# node.net
KiCad netlist of a schematic drawn in EAGLE
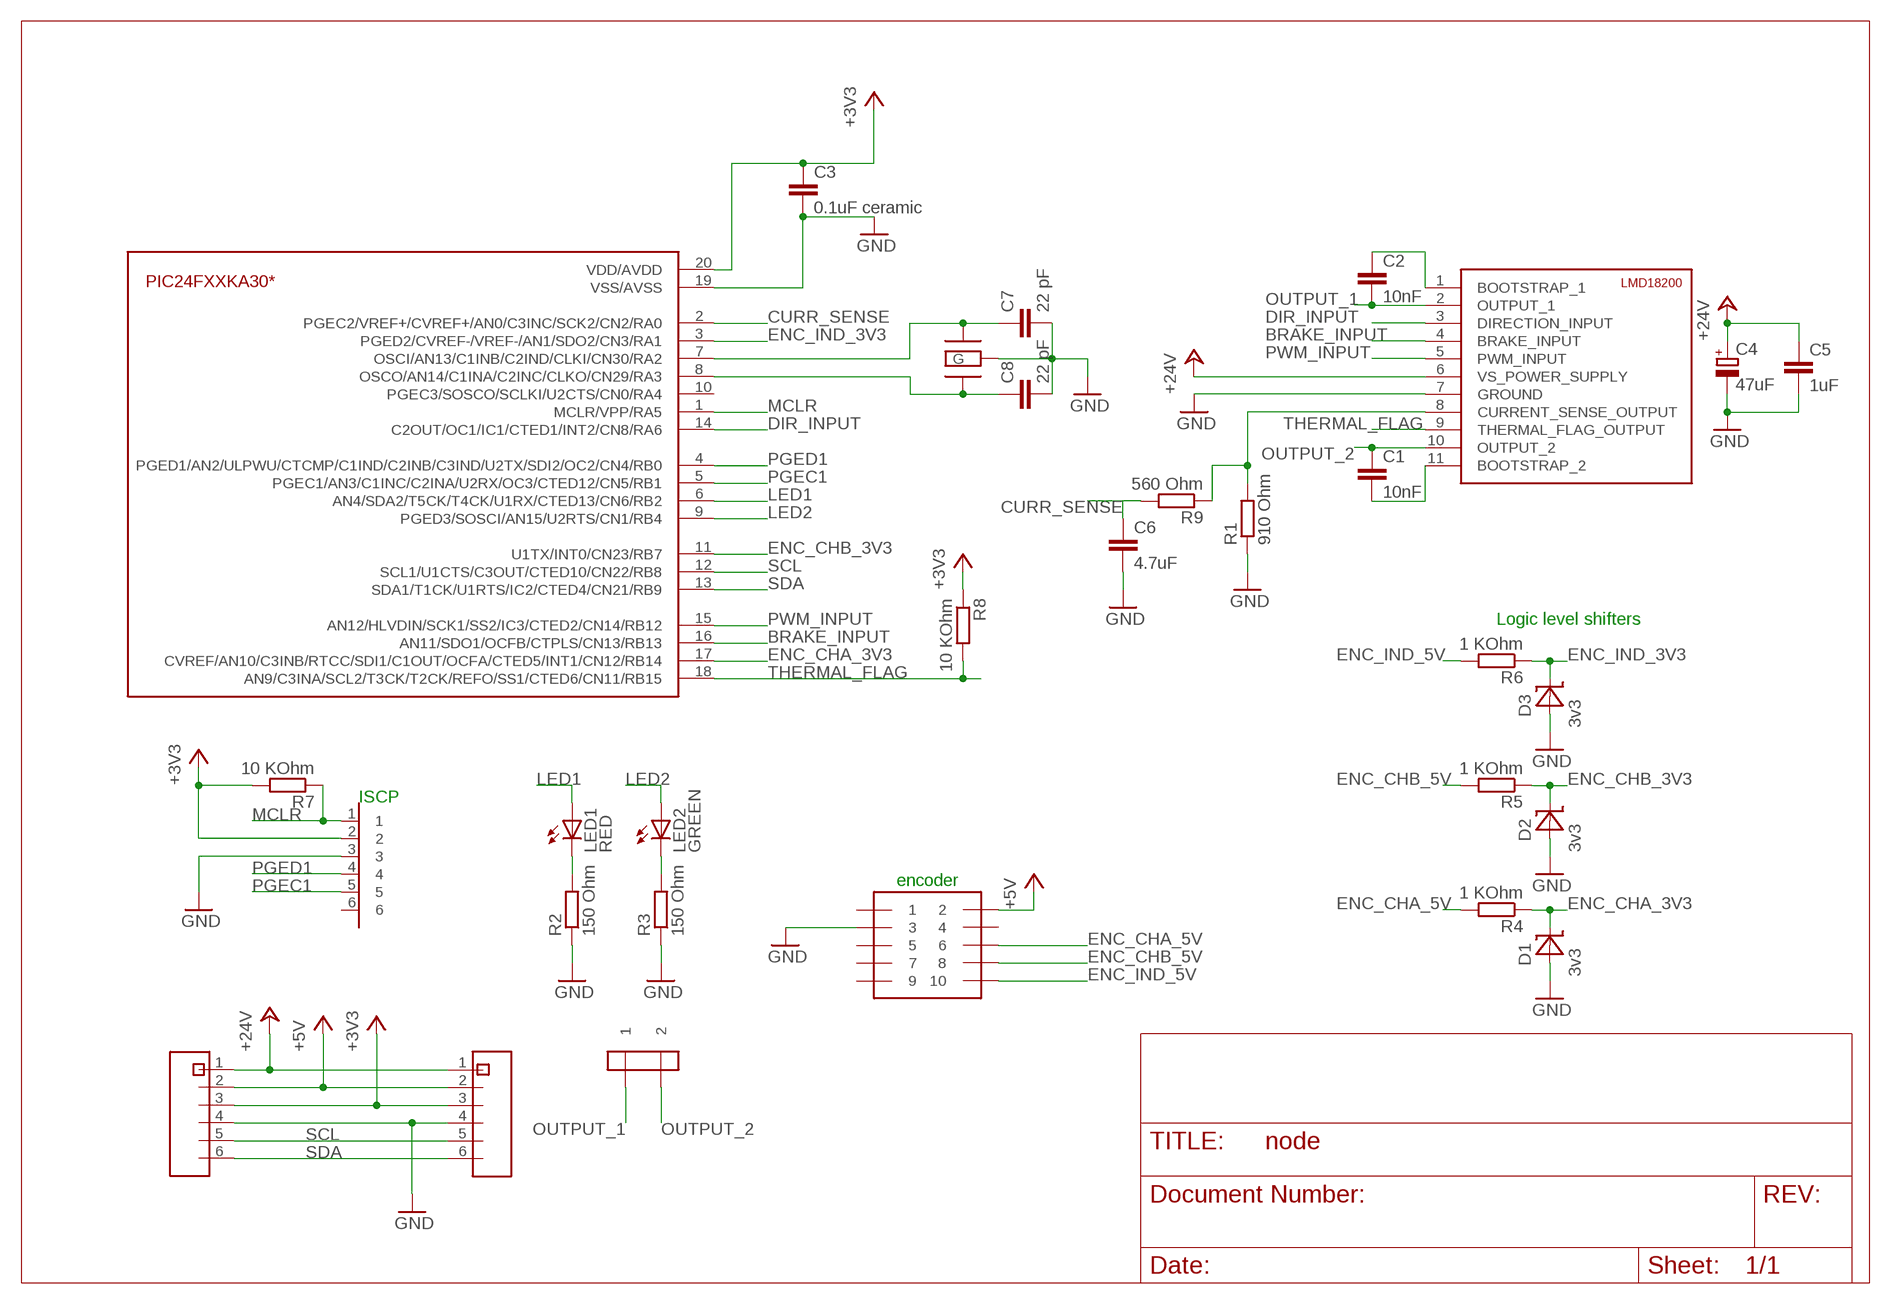
[diagram p0: schematic, sheet 1]

(export (version "E")
  (design (tool "Eeschema 10.0.6"))
  (components
    (comp (ref "C1")
      (value "10nF")
      (footprint "eagle-import:C0603")
      (libsource (lib "eagle-import") (part "resistor_C-EUC0603"))
    )
    (comp (ref "C2")
      (value "10nF")
      (footprint "eagle-import:C0603")
      (libsource (lib "eagle-import") (part "resistor_C-EUC0603"))
    )
    (comp (ref "C3")
      (value "0.1uF ceramic")
      (footprint "eagle-import:C0805K")
      (libsource (lib "eagle-import") (part "resistor_C-EUC0805K"))
    )
    (comp (ref "C4")
      (value "47uF")
      (footprint "eagle-import:E5-10,5")
      (libsource (lib "eagle-import") (part "CPOL-EUE5-10.5"))
    )
    (comp (ref "C5")
      (value "1uF")
      (footprint "eagle-import:C050-025X075")
      (libsource (lib "eagle-import") (part "C-EU050-025X075"))
    )
    (comp (ref "C6")
      (value "4.7uF")
      (footprint "eagle-import:C0805K")
      (libsource (lib "eagle-import") (part "resistor_C-EUC0805K"))
    )
    (comp (ref "C7")
      (value "22 pF")
      (footprint "eagle-import:C0603")
      (libsource (lib "eagle-import") (part "C-EUC0603"))
    )
    (comp (ref "C8")
      (value "22 pF")
      (footprint "eagle-import:C0603")
      (libsource (lib "eagle-import") (part "C-EUC0603"))
    )
    (comp (ref "D1")
      (value "3v3")
      (footprint "eagle-import:SOD-323")
      (libsource (lib "eagle-import") (part "ZENER_SOD323"))
    )
    (comp (ref "D2")
      (value "3v3")
      (footprint "eagle-import:SOD-323")
      (libsource (lib "eagle-import") (part "ZENER_SOD323"))
    )
    (comp (ref "D3")
      (value "3v3")
      (footprint "eagle-import:SOD-323")
      (libsource (lib "eagle-import") (part "ZENER_SOD323"))
    )
    (comp (ref "LED1")
      (value "RED")
      (footprint "eagle-import:CHIPLED_1206")
      (libsource (lib "eagle-import") (part "LEDCHIPLED_1206"))
    )
    (comp (ref "LED2")
      (value "GREEN")
      (footprint "eagle-import:CHIPLED_1206")
      (libsource (lib "eagle-import") (part "LEDCHIPLED_1206"))
    )
    (comp (ref "R1")
      (value "910 Ohm")
      (footprint "eagle-import:R0603")
      (libsource (lib "eagle-import") (part "R-EU_R0603"))
    )
    (comp (ref "R2")
      (value "150 Ohm")
      (footprint "eagle-import:R0603")
      (libsource (lib "eagle-import") (part "R-EU_R0603"))
    )
    (comp (ref "R3")
      (value "150 Ohm")
      (footprint "eagle-import:R0603")
      (libsource (lib "eagle-import") (part "R-EU_R0603"))
    )
    (comp (ref "R4")
      (value "1 KOhm")
      (footprint "eagle-import:R0603")
      (libsource (lib "eagle-import") (part "R-EU_R0603"))
    )
    (comp (ref "R5")
      (value "1 KOhm")
      (footprint "eagle-import:R0603")
      (libsource (lib "eagle-import") (part "R-EU_R0603"))
    )
    (comp (ref "R6")
      (value "1 KOhm")
      (footprint "eagle-import:R0603")
      (libsource (lib "eagle-import") (part "R-EU_R0603"))
    )
    (comp (ref "R7")
      (value "10 KOhm")
      (footprint "eagle-import:R0603")
      (libsource (lib "eagle-import") (part "R-EU_R0603"))
    )
    (comp (ref "R8")
      (value "10 KOhm")
      (footprint "eagle-import:R0603")
      (libsource (lib "eagle-import") (part "R-EU_R0603"))
    )
    (comp (ref "R9")
      (value "560 Ohm")
      (footprint "eagle-import:R0603")
      (libsource (lib "eagle-import") (part "R-EU_R0603"))
    )
    (comp (ref "U$1")
      (value "PIC24F32KA301")
      (footprint "eagle-import:SSOP-20")
      (libsource (lib "eagle-import") (part "PIC24F32KA301"))
    )
    (comp (ref "U$2")
      (value "LMD18200")
      (footprint "eagle-import:TO-220-11")
      (libsource (lib "eagle-import") (part "LMD18200"))
    )
    (comp (ref "U$3")
      (value "MOLEX_3.96MM_6P")
      (footprint "eagle-import:MOLEX_3.96MM_6P")
      (libsource (lib "eagle-import") (part "MOLEX_3.96MM_6P"))
    )
    (comp (ref "U$4")
      (value "MOLEX_3.96MM_6P")
      (footprint "eagle-import:MOLEX_3.96MM_6P")
      (libsource (lib "eagle-import") (part "MOLEX_3.96MM_6P"))
    )
    (comp (ref "U$5")
      (value "DIN41651_10P")
      (footprint "eagle-import:DIN41651_10P")
      (libsource (lib "eagle-import") (part "DIN41651_10P"))
    )
    (comp (ref "U$6")
      (value "STIFTLIST_6X1P")
      (footprint "eagle-import:STIFTLIST_6X1P")
      (libsource (lib "eagle-import") (part "STIFTLIST_6X1P"))
    )
    (comp (ref "U$7")
      (value "CRYSTAL_ELFA")
      (footprint "eagle-import:CRYSTAL_SMD")
      (libsource (lib "eagle-import") (part "CRYSTAL_ELFA"))
    )
    (comp (ref "U$8")
      (value "PCB_SKRUVPLINT_2P")
      (footprint "eagle-import:PCB_SKRUVPLINT_2P")
      (libsource (lib "eagle-import") (part "PCB_SKRUVPLINT_2P"))
    )
  )
  (nets
    (net (code "1") (name "+3V3") (class "Default")
      (node (ref "C3") (pin "1") (pinfunction "1_1") (pintype "passive"))
      (node (ref "R7") (pin "2") (pinfunction "2_2") (pintype "passive"))
      (node (ref "R8") (pin "1") (pinfunction "1_1") (pintype "passive"))
      (node (ref "U$1") (pin "20") (pinfunction "VDD/AVDD_20") (pintype "bidirectional"))
      (node (ref "U$3") (pin "3") (pinfunction "3_3") (pintype "bidirectional"))
      (node (ref "U$4") (pin "3") (pinfunction "3_3") (pintype "bidirectional"))
      (node (ref "U$6") (pin "2") (pinfunction "2_2") (pintype "bidirectional"))
    )
    (net (code "2") (name "+5V") (class "Default")
      (node (ref "U$3") (pin "2") (pinfunction "2_2") (pintype "bidirectional"))
      (node (ref "U$4") (pin "2") (pinfunction "2_2") (pintype "bidirectional"))
      (node (ref "U$5") (pin "2") (pinfunction "2_2") (pintype "bidirectional"))
    )
    (net (code "3") (name "+24V") (class "Default")
      (node (ref "C4") (pin "+") (pinfunction "+_+") (pintype "passive"))
      (node (ref "C5") (pin "1") (pinfunction "1_1") (pintype "passive"))
      (node (ref "U$2") (pin "6") (pinfunction "VS_POWER_SUPPLY_6") (pintype "bidirectional"))
      (node (ref "U$3") (pin "1") (pinfunction "1_1") (pintype "bidirectional"))
      (node (ref "U$4") (pin "1") (pinfunction "1_1") (pintype "bidirectional"))
    )
    (net (code "4") (name "/BRAKE_INPUT") (class "Default")
      (node (ref "U$1") (pin "16") (pinfunction "AN11/SDO1/OCFB/CTPLS/CN13/RB13_16") (pintype "bidirectional"))
      (node (ref "U$2") (pin "4") (pinfunction "BRAKE_INPUT_4") (pintype "bidirectional"))
    )
    (net (code "5") (name "/CURR_SENSE") (class "Default")
      (node (ref "C6") (pin "1") (pinfunction "1_1") (pintype "passive"))
      (node (ref "R9") (pin "2") (pinfunction "2_2") (pintype "passive"))
      (node (ref "U$1") (pin "2") (pinfunction "PGEC2/VREF+/CVREF+/AN0/C3INC/SCK2/CN2/RA0_2") (pintype "bidirectional"))
    )
    (net (code "6") (name "/DIR_INPUT") (class "Default")
      (node (ref "U$1") (pin "14") (pinfunction "C2OUT/OC1/IC1/CTED1/INT2/CN8/RA6_14") (pintype "bidirectional"))
      (node (ref "U$2") (pin "3") (pinfunction "DIRECTION_INPUT_3") (pintype "bidirectional"))
    )
    (net (code "7") (name "/ENC_CHA_3V3") (class "Default")
      (node (ref "D1") (pin "C") (pinfunction "C_C") (pintype "passive"))
      (node (ref "R4") (pin "1") (pinfunction "1_1") (pintype "passive"))
      (node (ref "U$1") (pin "17") (pinfunction "CVREF/AN10/C3INB/RTCC/SDI1/C1OUT/OCFA/CTED5/INT1/CN12/RB14_17") (pintype "bidirectional"))
    )
    (net (code "8") (name "/ENC_CHA_5V") (class "Default")
      (node (ref "R4") (pin "2") (pinfunction "2_2") (pintype "passive"))
      (node (ref "U$5") (pin "6") (pinfunction "6_6") (pintype "bidirectional"))
    )
    (net (code "9") (name "/ENC_CHB_3V3") (class "Default")
      (node (ref "D2") (pin "C") (pinfunction "C_C") (pintype "passive"))
      (node (ref "R5") (pin "1") (pinfunction "1_1") (pintype "passive"))
      (node (ref "U$1") (pin "11") (pinfunction "U1TX/INT0/CN23/RB7_11") (pintype "bidirectional"))
    )
    (net (code "10") (name "/ENC_CHB_5V") (class "Default")
      (node (ref "R5") (pin "2") (pinfunction "2_2") (pintype "passive"))
      (node (ref "U$5") (pin "8") (pinfunction "8_8") (pintype "bidirectional"))
    )
    (net (code "11") (name "/ENC_IND_3V3") (class "Default")
      (node (ref "D3") (pin "C") (pinfunction "C_C") (pintype "passive"))
      (node (ref "R6") (pin "1") (pinfunction "1_1") (pintype "passive"))
      (node (ref "U$1") (pin "3") (pinfunction "PGED2/CVREF-/VREF-/AN1/SDO2/CN3/RA1_3") (pintype "bidirectional"))
    )
    (net (code "12") (name "/ENC_IND_5V") (class "Default")
      (node (ref "R6") (pin "2") (pinfunction "2_2") (pintype "passive"))
      (node (ref "U$5") (pin "10") (pinfunction "10_10") (pintype "bidirectional"))
    )
    (net (code "13") (name "/LED1") (class "Default")
      (node (ref "LED1") (pin "A") (pinfunction "A_A") (pintype "passive"))
      (node (ref "U$1") (pin "6") (pinfunction "AN4/SDA2/T5CK/T4CK/U1RX/CTED13/CN6/RB2_6") (pintype "bidirectional"))
    )
    (net (code "14") (name "/LED2") (class "Default")
      (node (ref "LED2") (pin "A") (pinfunction "A_A") (pintype "passive"))
      (node (ref "U$1") (pin "9") (pinfunction "PGED3/SOSCI/AN15/U2RTS/CN1/RB4_9") (pintype "bidirectional"))
    )
    (net (code "15") (name "/MCLR") (class "Default")
      (node (ref "R7") (pin "1") (pinfunction "1_1") (pintype "passive"))
      (node (ref "U$1") (pin "1") (pinfunction "MCLR/VPP/RA5_1") (pintype "bidirectional"))
      (node (ref "U$6") (pin "1") (pinfunction "1_1") (pintype "bidirectional"))
    )
    (net (code "16") (name "/OUTPUT_1") (class "Default")
      (node (ref "C2") (pin "2") (pinfunction "2_2") (pintype "passive"))
      (node (ref "U$2") (pin "2") (pinfunction "OUTPUT_1_2") (pintype "bidirectional"))
      (node (ref "U$8") (pin "1") (pinfunction "1_1") (pintype "bidirectional"))
    )
    (net (code "17") (name "/OUTPUT_2") (class "Default")
      (node (ref "C1") (pin "1") (pinfunction "1_1") (pintype "passive"))
      (node (ref "U$2") (pin "10") (pinfunction "OUTPUT_2_10") (pintype "bidirectional"))
      (node (ref "U$8") (pin "2") (pinfunction "2_2") (pintype "bidirectional"))
    )
    (net (code "18") (name "/PGEC1") (class "Default")
      (node (ref "U$1") (pin "5") (pinfunction "PGEC1/AN3/C1INC/C2INA/U2RX/OC3/CTED12/CN5/RB1_5") (pintype "bidirectional"))
      (node (ref "U$6") (pin "5") (pinfunction "5_5") (pintype "bidirectional"))
    )
    (net (code "19") (name "/PGED1") (class "Default")
      (node (ref "U$1") (pin "4") (pinfunction "PGED1/AN2/ULPWU/CTCMP/C1IND/C2INB/C3IND/U2TX/SDI2/OC2/CN4/RB0_4") (pintype "bidirectional"))
      (node (ref "U$6") (pin "4") (pinfunction "4_4") (pintype "bidirectional"))
    )
    (net (code "20") (name "/PWM_INPUT") (class "Default")
      (node (ref "U$1") (pin "15") (pinfunction "AN12/HLVDIN/SCK1/SS2/IC3/CTED2/CN14/RB12_15") (pintype "bidirectional"))
      (node (ref "U$2") (pin "5") (pinfunction "PWM_INPUT_5") (pintype "bidirectional"))
    )
    (net (code "21") (name "/SCL") (class "Default")
      (node (ref "U$1") (pin "12") (pinfunction "SCL1/U1CTS/C3OUT/CTED10/CN22/RB8_12") (pintype "bidirectional"))
      (node (ref "U$3") (pin "5") (pinfunction "5_5") (pintype "bidirectional"))
      (node (ref "U$4") (pin "5") (pinfunction "5_5") (pintype "bidirectional"))
    )
    (net (code "22") (name "/SDA") (class "Default")
      (node (ref "U$1") (pin "13") (pinfunction "SDA1/T1CK/U1RTS/IC2/CTED4/CN21/RB9_13") (pintype "bidirectional"))
      (node (ref "U$3") (pin "6") (pinfunction "6_6") (pintype "bidirectional"))
      (node (ref "U$4") (pin "6") (pinfunction "6_6") (pintype "bidirectional"))
    )
    (net (code "23") (name "/THERMAL_FLAG") (class "Default")
      (node (ref "R8") (pin "2") (pinfunction "2_2") (pintype "passive"))
      (node (ref "U$1") (pin "18") (pinfunction "AN9/C3INA/SCL2/T3CK/T2CK/REFO/SS1/CTED6/CN11/RB15_18") (pintype "bidirectional"))
      (node (ref "U$2") (pin "9") (pinfunction "THERMAL_FLAG_OUTPUT_9") (pintype "bidirectional"))
    )
    (net (code "24") (name "GND") (class "Default")
      (node (ref "C3") (pin "2") (pinfunction "2_2") (pintype "passive"))
      (node (ref "C4") (pin "-") (pinfunction "-_-") (pintype "passive"))
      (node (ref "C5") (pin "2") (pinfunction "2_2") (pintype "passive"))
      (node (ref "C6") (pin "2") (pinfunction "2_2") (pintype "passive"))
      (node (ref "C7") (pin "2") (pinfunction "2_2") (pintype "passive"))
      (node (ref "C8") (pin "2") (pinfunction "2_2") (pintype "passive"))
      (node (ref "D1") (pin "A") (pinfunction "A_A") (pintype "passive"))
      (node (ref "D2") (pin "A") (pinfunction "A_A") (pintype "passive"))
      (node (ref "D3") (pin "A") (pinfunction "A_A") (pintype "passive"))
      (node (ref "R1") (pin "1") (pinfunction "1_1") (pintype "passive"))
      (node (ref "R2") (pin "1") (pinfunction "1_1") (pintype "passive"))
      (node (ref "R3") (pin "1") (pinfunction "1_1") (pintype "passive"))
      (node (ref "U$1") (pin "19") (pinfunction "VSS/AVSS_19") (pintype "bidirectional"))
      (node (ref "U$2") (pin "7") (pinfunction "GROUND_7") (pintype "bidirectional"))
      (node (ref "U$3") (pin "4") (pinfunction "4_4") (pintype "bidirectional"))
      (node (ref "U$4") (pin "4") (pinfunction "4_4") (pintype "bidirectional"))
      (node (ref "U$5") (pin "3") (pinfunction "3_3") (pintype "bidirectional"))
      (node (ref "U$6") (pin "3") (pinfunction "3_3") (pintype "bidirectional"))
      (node (ref "U$7") (pin "2") (pinfunction "G_2") (pintype "bidirectional"))
      (node (ref "U$7") (pin "4") (pinfunction "G_4") (pintype "bidirectional"))
    )
    (net (code "25") (name "Net-(LED1-PadC)") (class "Default")
      (node (ref "LED1") (pin "C") (pinfunction "C_C") (pintype "passive"))
      (node (ref "R2") (pin "2") (pinfunction "2_2") (pintype "passive"))
    )
    (net (code "26") (name "Net-(LED2-PadC)") (class "Default")
      (node (ref "LED2") (pin "C") (pinfunction "C_C") (pintype "passive"))
      (node (ref "R3") (pin "2") (pinfunction "2_2") (pintype "passive"))
    )
    (net (code "27") (name "Net-(U$1-OSCI{slash}AN13{slash}C1INB{slash}C2IND{slash}CLKI{slash}CN30{slash}RA2)") (class "Default")
      (node (ref "C7") (pin "1") (pinfunction "1_1") (pintype "passive"))
      (node (ref "U$1") (pin "7") (pinfunction "OSCI/AN13/C1INB/C2IND/CLKI/CN30/RA2_7") (pintype "bidirectional"))
      (node (ref "U$7") (pin "3") (pinfunction "CRYSTAL_2_3") (pintype "bidirectional"))
    )
    (net (code "28") (name "Net-(U$1-OSCO{slash}AN14{slash}C1INA{slash}C2INC{slash}CLKO{slash}CN29{slash}RA3)") (class "Default")
      (node (ref "C8") (pin "1") (pinfunction "1_1") (pintype "passive"))
      (node (ref "U$1") (pin "8") (pinfunction "OSCO/AN14/C1INA/C2INC/CLKO/CN29/RA3_8") (pintype "bidirectional"))
      (node (ref "U$7") (pin "1") (pinfunction "CRYSTAL_1_1") (pintype "bidirectional"))
    )
    (net (code "29") (name "Net-(U$2-BOOTSTRAP_1)") (class "Default")
      (node (ref "C2") (pin "1") (pinfunction "1_1") (pintype "passive"))
      (node (ref "U$2") (pin "1") (pinfunction "BOOTSTRAP_1_1") (pintype "bidirectional"))
    )
    (net (code "30") (name "Net-(U$2-BOOTSTRAP_2)") (class "Default")
      (node (ref "C1") (pin "2") (pinfunction "2_2") (pintype "passive"))
      (node (ref "U$2") (pin "11") (pinfunction "BOOTSTRAP_2_11") (pintype "bidirectional"))
    )
    (net (code "31") (name "Net-(U$2-CURRENT_SENSE_OUTPUT)") (class "Default")
      (node (ref "R1") (pin "2") (pinfunction "2_2") (pintype "passive"))
      (node (ref "R9") (pin "1") (pinfunction "1_1") (pintype "passive"))
      (node (ref "U$2") (pin "8") (pinfunction "CURRENT_SENSE_OUTPUT_8") (pintype "bidirectional"))
    )
    (net (code "32") (name "unconnected-(U$1-PGEC3{slash}SOSCO{slash}SCLKI{slash}U2CTS{slash}CN0{slash}RA4-Pad10)") (class "Default")
      (node (ref "U$1") (pin "10") (pinfunction "PGEC3/SOSCO/SCLKI/U2CTS/CN0/RA4_10") (pintype "bidirectional"))
    )
    (net (code "33") (name "unconnected-(U$5-Pad1)") (class "Default")
      (node (ref "U$5") (pin "1") (pinfunction "1_1") (pintype "bidirectional"))
    )
    (net (code "34") (name "unconnected-(U$5-Pad4)") (class "Default")
      (node (ref "U$5") (pin "4") (pinfunction "4_4") (pintype "bidirectional"))
    )
    (net (code "35") (name "unconnected-(U$5-Pad5)") (class "Default")
      (node (ref "U$5") (pin "5") (pinfunction "5_5") (pintype "bidirectional"))
    )
    (net (code "36") (name "unconnected-(U$5-Pad7)") (class "Default")
      (node (ref "U$5") (pin "7") (pinfunction "7_7") (pintype "bidirectional"))
    )
    (net (code "37") (name "unconnected-(U$5-Pad9)") (class "Default")
      (node (ref "U$5") (pin "9") (pinfunction "9_9") (pintype "bidirectional"))
    )
    (net (code "38") (name "unconnected-(U$6-Pad6)") (class "Default")
      (node (ref "U$6") (pin "6") (pinfunction "6_6") (pintype "bidirectional"))
    )
  )
)
